# 03_power.net
KiCad netlist of a schematic drawn in Altium Designer
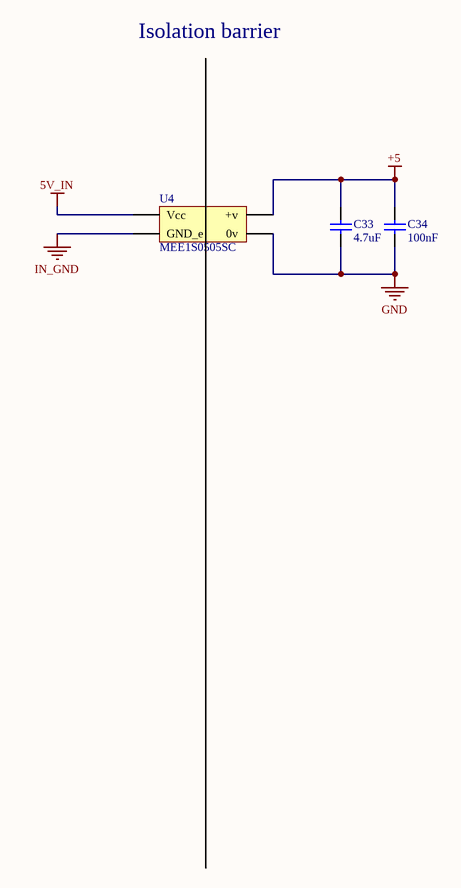
[diagram p0: 03_power.SchDoc]

(export (version "E")
  (design (tool "Eeschema 10.0.6"))
  (components
    (comp (ref "C33")
      (value "4.7uF")
      (footprint "C0402")
      (description "Capacitor, MLCC, 4.7uF, 6V3, X5R, 20%, 0402, T=0,5mm")
      (fields
        (field (name "INTERNAL_PART_NUMBER") "MCD-01356")
        (field (name "MANUFACTURER_PART_NUMBER") "GRM155R60J475ME47")
        (field (name "PROVIDED_BY") "Subcon")
      )
      (libsource (lib "MCD_PARTS_database") (part "Capacitor"))
    )
    (comp (ref "C34")
      (value "100nF")
      (footprint "C0603")
      (description "Capacitor, MLCC, 100nF, 16V, X7R, 10%, 0402, T=0,5mm")
      (fields
        (field (name "INTERNAL_PART_NUMBER") "MCD-00102")
        (field (name "MANUFACTURER_PART_NUMBER") "CC0402KRX7R7BB104")
        (field (name "PROVIDED_BY") "SUBCO")
      )
      (libsource (lib "MCD_PARTS_database") (part "Capacitor"))
    )
    (comp (ref "U4")
      (value "MEE1S0505SC")
      (footprint "DCDC")
      (description "DCDC")
      (libsource (lib "Project_PIER002.1.1") (part "DCDC"))
    )
  )
  (nets
    (net (code "1") (name "+5") (class "Default")
      (node (ref "C33") (pin "2") (pinfunction "2_2") (pintype "passive"))
      (node (ref "C34") (pin "2") (pinfunction "2_2") (pintype "passive"))
      (node (ref "U4") (pin "4") (pinfunction "+v_4") (pintype "passive"))
    )
    (net (code "2") (name "5V_IN") (class "Default")
      (node (ref "U4") (pin "2") (pinfunction "Vcc_2") (pintype "passive"))
    )
    (net (code "3") (name "GND") (class "Default")
      (node (ref "C33") (pin "1") (pinfunction "1_1") (pintype "passive"))
      (node (ref "C34") (pin "1") (pinfunction "1_1") (pintype "passive"))
      (node (ref "U4") (pin "3") (pinfunction "0v_3") (pintype "passive"))
    )
    (net (code "4") (name "IN_GND") (class "Default")
      (node (ref "U4") (pin "1") (pinfunction "GND_e_1") (pintype "passive"))
    )
  )
)
